# Block_Template.net
KiCad netlist of a schematic drawn in EAGLE
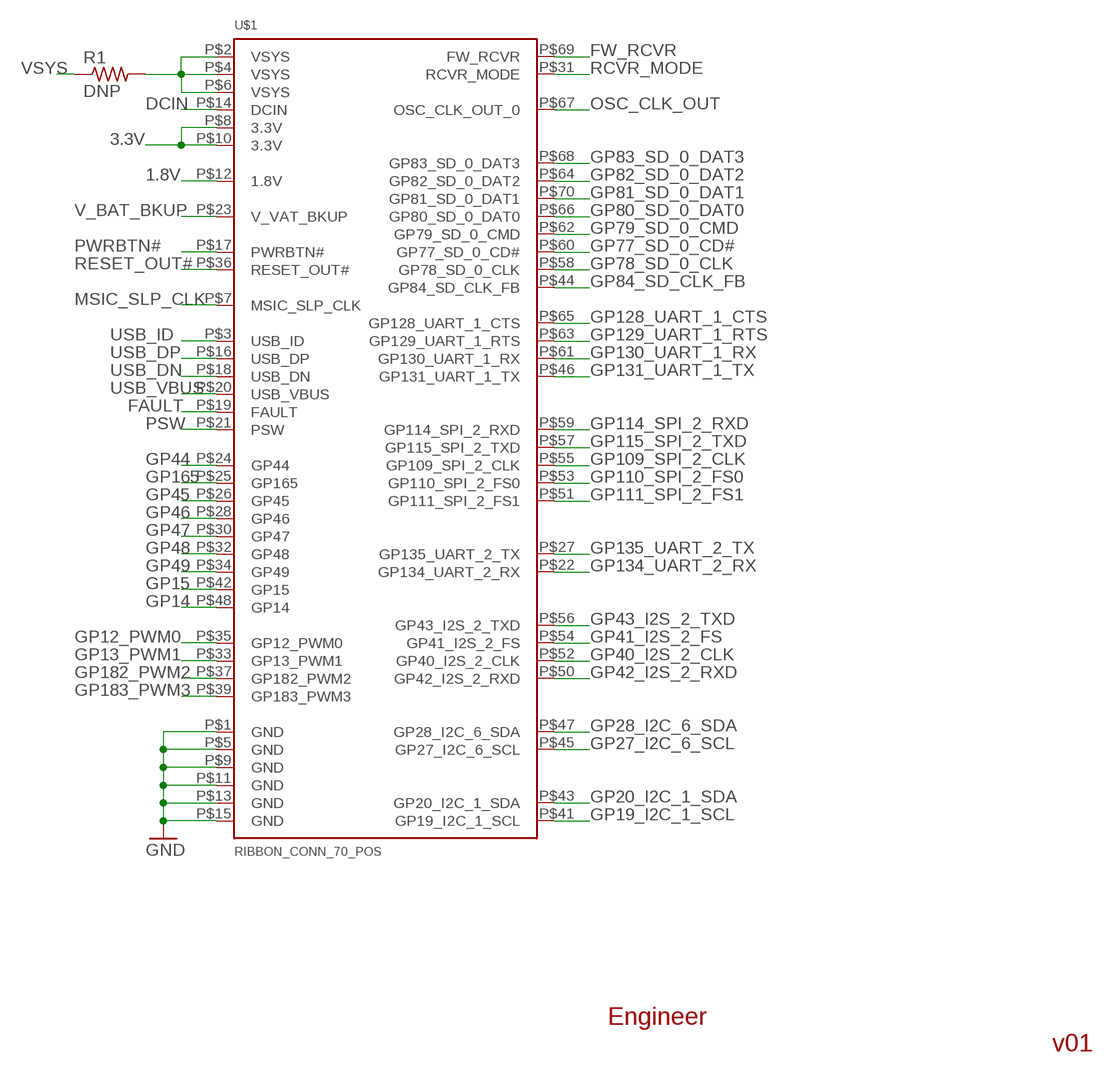
[diagram p0: schematic, sheet 1]
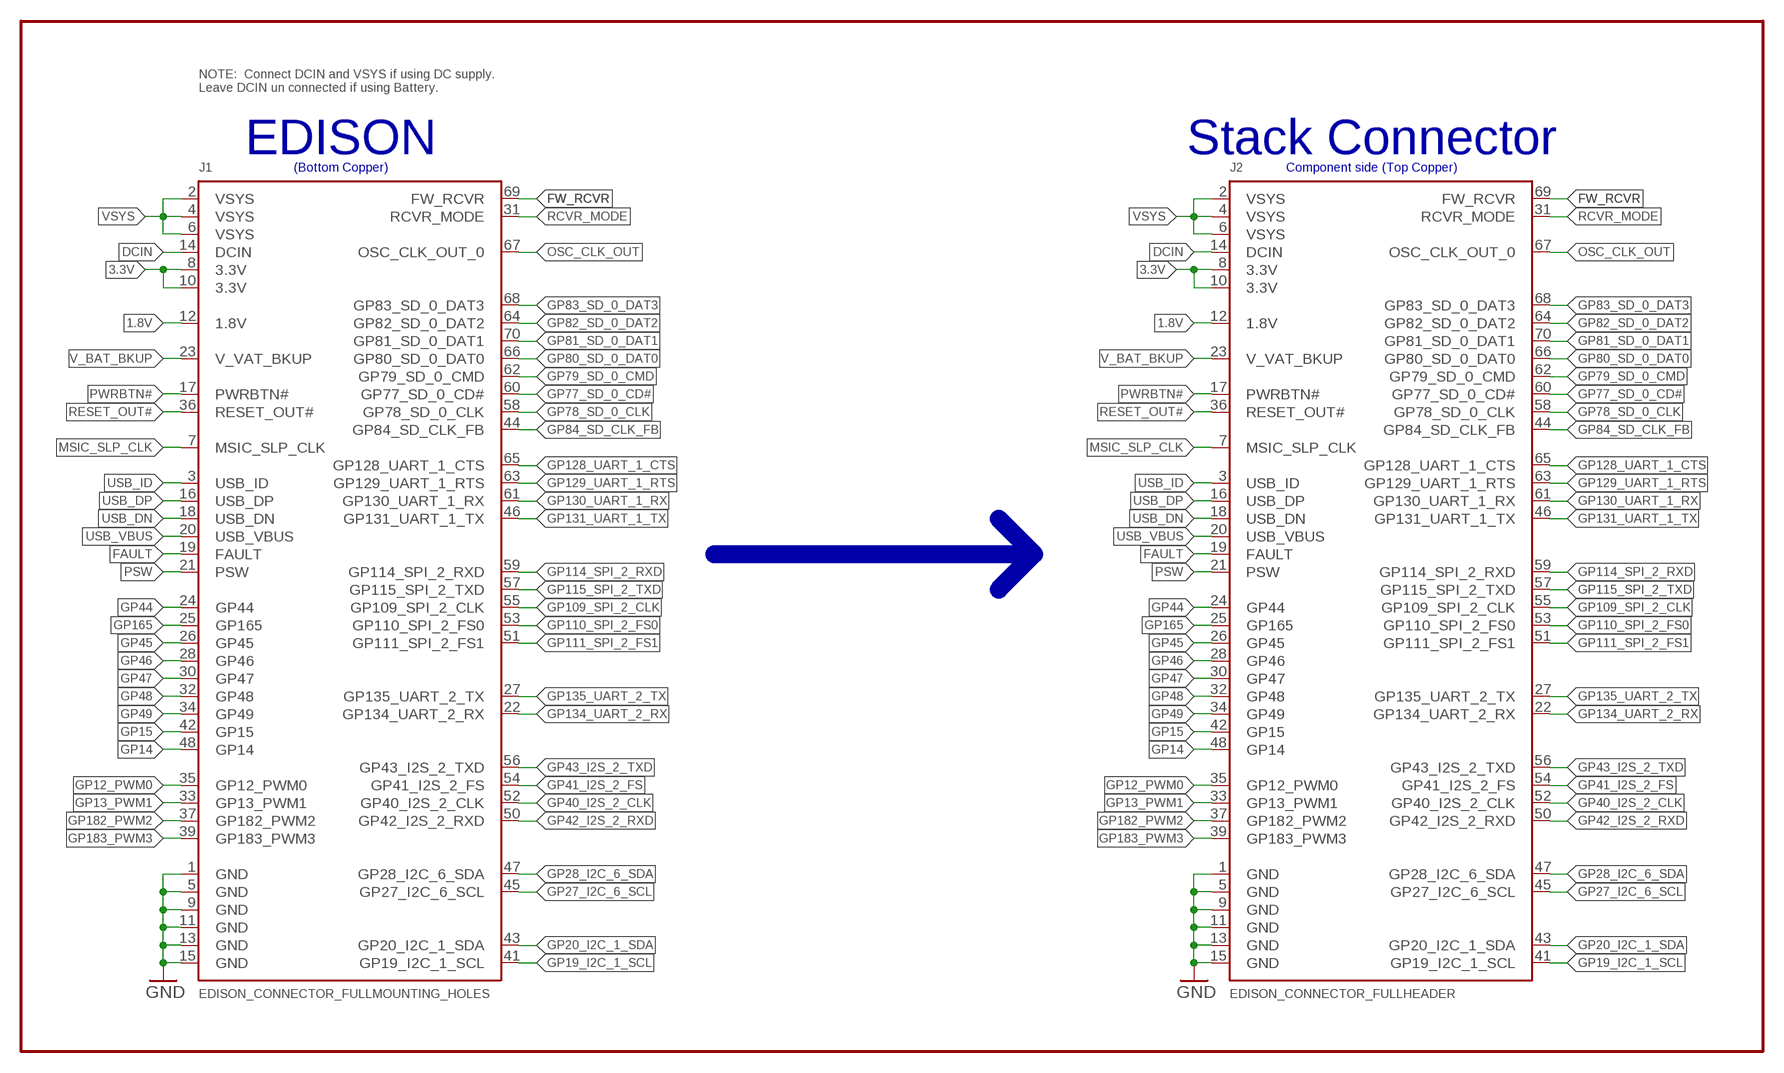
[diagram p1: schematic, sheet 2]

(export (version "E")
  (design (tool "Eeschema 10.0.6"))
  (components
    (comp (ref "J1")
      (value "EDISON_CONNECTOR_FULLMOUNTING_HOLES")
      (footprint "eagle-import:EDISON_DAUGHTER")
      (libsource (lib "eagle-import") (part "EDISON_CONNECTOR_FULLMOUNTING_HOLES"))
    )
    (comp (ref "J2")
      (value "EDISON_CONNECTOR_FULLHEADER")
      (footprint "eagle-import:DF40C-70DP-0.4(51)")
      (libsource (lib "eagle-import") (part "EDISON_CONNECTOR_FULLHEADER"))
    )
    (comp (ref "R1")
      (value "DNP")
      (footprint "eagle-import:R0402")
      (libsource (lib "eagle-import") (part "R-US_R0402"))
    )
    (comp (ref "U$1")
      (value "RIBBON_CONN_70_POS")
      (footprint "eagle-import:RIBBON_CONN_70_POS")
      (libsource (lib "eagle-import") (part "RIBBON_CONN_70_POS"))
    )
  )
  (nets
    (net (code "1") (name "1.8V") (class "Default")
      (node (ref "J1") (pin "12") (pinfunction "1.8V_12") (pintype "bidirectional"))
      (node (ref "J2") (pin "12") (pinfunction "1.8V_12") (pintype "bidirectional"))
      (node (ref "U$1") (pin "P$12") (pinfunction "1.8V_P$12") (pintype "bidirectional"))
    )
    (net (code "2") (name "3.3V") (class "Default")
      (node (ref "J1") (pin "10") (pinfunction "3.3V_10") (pintype "bidirectional"))
      (node (ref "J1") (pin "8") (pinfunction "3.3V_8") (pintype "bidirectional"))
      (node (ref "J2") (pin "10") (pinfunction "3.3V_10") (pintype "bidirectional"))
      (node (ref "J2") (pin "8") (pinfunction "3.3V_8") (pintype "bidirectional"))
      (node (ref "U$1") (pin "P$10") (pinfunction "3.3V_P$10") (pintype "bidirectional"))
      (node (ref "U$1") (pin "P$8") (pinfunction "3.3V_P$8") (pintype "bidirectional"))
    )
    (net (code "3") (name "DCIN") (class "Default")
      (node (ref "J1") (pin "14") (pinfunction "DCIN_14") (pintype "bidirectional"))
      (node (ref "J2") (pin "14") (pinfunction "DCIN_14") (pintype "bidirectional"))
      (node (ref "U$1") (pin "P$14") (pinfunction "DCIN_P$14") (pintype "bidirectional"))
    )
    (net (code "4") (name "FAULT") (class "Default")
      (node (ref "J1") (pin "19") (pinfunction "FAULT_19") (pintype "bidirectional"))
      (node (ref "J2") (pin "19") (pinfunction "FAULT_19") (pintype "bidirectional"))
      (node (ref "U$1") (pin "P$19") (pinfunction "FAULT_P$19") (pintype "bidirectional"))
    )
    (net (code "5") (name "FW_RCVR") (class "Default")
      (node (ref "J1") (pin "69") (pinfunction "FW_RCVR_69") (pintype "bidirectional"))
      (node (ref "J2") (pin "69") (pinfunction "FW_RCVR_69") (pintype "bidirectional"))
      (node (ref "U$1") (pin "P$69") (pinfunction "FW_RCVR_P$69") (pintype "bidirectional"))
    )
    (net (code "6") (name "GND") (class "Default")
      (node (ref "J1") (pin "1") (pinfunction "GND_1") (pintype "bidirectional"))
      (node (ref "J1") (pin "11") (pinfunction "GND_11") (pintype "bidirectional"))
      (node (ref "J1") (pin "13") (pinfunction "GND_13") (pintype "bidirectional"))
      (node (ref "J1") (pin "15") (pinfunction "GND_15") (pintype "bidirectional"))
      (node (ref "J1") (pin "5") (pinfunction "GND_5") (pintype "bidirectional"))
      (node (ref "J1") (pin "9") (pinfunction "GND_9") (pintype "bidirectional"))
      (node (ref "J2") (pin "1") (pinfunction "GND_1") (pintype "bidirectional"))
      (node (ref "J2") (pin "11") (pinfunction "GND_11") (pintype "bidirectional"))
      (node (ref "J2") (pin "13") (pinfunction "GND_13") (pintype "bidirectional"))
      (node (ref "J2") (pin "15") (pinfunction "GND_15") (pintype "bidirectional"))
      (node (ref "J2") (pin "5") (pinfunction "GND_5") (pintype "bidirectional"))
      (node (ref "J2") (pin "9") (pinfunction "GND_9") (pintype "bidirectional"))
      (node (ref "U$1") (pin "P$1") (pinfunction "GND_P$1") (pintype "bidirectional"))
      (node (ref "U$1") (pin "P$11") (pinfunction "GND_P$11") (pintype "bidirectional"))
      (node (ref "U$1") (pin "P$13") (pinfunction "GND_P$13") (pintype "bidirectional"))
      (node (ref "U$1") (pin "P$15") (pinfunction "GND_P$15") (pintype "bidirectional"))
      (node (ref "U$1") (pin "P$5") (pinfunction "GND_P$5") (pintype "bidirectional"))
      (node (ref "U$1") (pin "P$9") (pinfunction "GND_P$9") (pintype "bidirectional"))
    )
    (net (code "7") (name "GP12_PWM0") (class "Default")
      (node (ref "J1") (pin "35") (pinfunction "GP12_PWM0_35") (pintype "bidirectional"))
      (node (ref "J2") (pin "35") (pinfunction "GP12_PWM0_35") (pintype "bidirectional"))
      (node (ref "U$1") (pin "P$35") (pinfunction "GP12_PWM0_P$35") (pintype "bidirectional"))
    )
    (net (code "8") (name "GP13_PWM1") (class "Default")
      (node (ref "J1") (pin "33") (pinfunction "GP13_PWM1_33") (pintype "bidirectional"))
      (node (ref "J2") (pin "33") (pinfunction "GP13_PWM1_33") (pintype "bidirectional"))
      (node (ref "U$1") (pin "P$33") (pinfunction "GP13_PWM1_P$33") (pintype "bidirectional"))
    )
    (net (code "9") (name "GP14") (class "Default")
      (node (ref "J1") (pin "48") (pinfunction "GP14_48") (pintype "bidirectional"))
      (node (ref "J2") (pin "48") (pinfunction "GP14_48") (pintype "bidirectional"))
      (node (ref "U$1") (pin "P$48") (pinfunction "GP14_P$48") (pintype "bidirectional"))
    )
    (net (code "10") (name "GP15") (class "Default")
      (node (ref "J1") (pin "42") (pinfunction "GP15_42") (pintype "bidirectional"))
      (node (ref "J2") (pin "42") (pinfunction "GP15_42") (pintype "bidirectional"))
      (node (ref "U$1") (pin "P$42") (pinfunction "GP15_P$42") (pintype "bidirectional"))
    )
    (net (code "11") (name "GP19_I2C_1_SCL") (class "Default")
      (node (ref "J1") (pin "41") (pinfunction "GP19_I2C_1_SCL_41") (pintype "bidirectional"))
      (node (ref "J2") (pin "41") (pinfunction "GP19_I2C_1_SCL_41") (pintype "bidirectional"))
      (node (ref "U$1") (pin "P$41") (pinfunction "GP19_I2C_1_SCL_P$41") (pintype "bidirectional"))
    )
    (net (code "12") (name "GP20_I2C_1_SDA") (class "Default")
      (node (ref "J1") (pin "43") (pinfunction "GP20_I2C_1_SDA_43") (pintype "bidirectional"))
      (node (ref "J2") (pin "43") (pinfunction "GP20_I2C_1_SDA_43") (pintype "bidirectional"))
      (node (ref "U$1") (pin "P$43") (pinfunction "GP20_I2C_1_SDA_P$43") (pintype "bidirectional"))
    )
    (net (code "13") (name "GP27_I2C_6_SCL") (class "Default")
      (node (ref "J1") (pin "45") (pinfunction "GP27_I2C_6_SCL_45") (pintype "bidirectional"))
      (node (ref "J2") (pin "45") (pinfunction "GP27_I2C_6_SCL_45") (pintype "bidirectional"))
      (node (ref "U$1") (pin "P$45") (pinfunction "GP27_I2C_6_SCL_P$45") (pintype "bidirectional"))
    )
    (net (code "14") (name "GP28_I2C_6_SDA") (class "Default")
      (node (ref "J1") (pin "47") (pinfunction "GP28_I2C_6_SDA_47") (pintype "bidirectional"))
      (node (ref "J2") (pin "47") (pinfunction "GP28_I2C_6_SDA_47") (pintype "bidirectional"))
      (node (ref "U$1") (pin "P$47") (pinfunction "GP28_I2C_6_SDA_P$47") (pintype "bidirectional"))
    )
    (net (code "15") (name "GP40_I2S_2_CLK") (class "Default")
      (node (ref "J1") (pin "52") (pinfunction "GP40_I2S_2_CLK_52") (pintype "bidirectional"))
      (node (ref "J2") (pin "52") (pinfunction "GP40_I2S_2_CLK_52") (pintype "bidirectional"))
      (node (ref "U$1") (pin "P$52") (pinfunction "GP40_I2S_2_CLK_P$52") (pintype "bidirectional"))
    )
    (net (code "16") (name "GP41_I2S_2_FS") (class "Default")
      (node (ref "J1") (pin "54") (pinfunction "GP41_I2S_2_FS_54") (pintype "bidirectional"))
      (node (ref "J2") (pin "54") (pinfunction "GP41_I2S_2_FS_54") (pintype "bidirectional"))
      (node (ref "U$1") (pin "P$54") (pinfunction "GP41_I2S_2_FS_P$54") (pintype "bidirectional"))
    )
    (net (code "17") (name "GP42_I2S_2_RXD") (class "Default")
      (node (ref "J1") (pin "50") (pinfunction "GP42_I2S_2_RXD_50") (pintype "bidirectional"))
      (node (ref "J2") (pin "50") (pinfunction "GP42_I2S_2_RXD_50") (pintype "bidirectional"))
      (node (ref "U$1") (pin "P$50") (pinfunction "GP42_I2S_2_RXD_P$50") (pintype "bidirectional"))
    )
    (net (code "18") (name "GP43_I2S_2_TXD") (class "Default")
      (node (ref "J1") (pin "56") (pinfunction "GP43_I2S_2_TXD_56") (pintype "bidirectional"))
      (node (ref "J2") (pin "56") (pinfunction "GP43_I2S_2_TXD_56") (pintype "bidirectional"))
      (node (ref "U$1") (pin "P$56") (pinfunction "GP43_I2S_2_TXD_P$56") (pintype "bidirectional"))
    )
    (net (code "19") (name "GP44") (class "Default")
      (node (ref "J1") (pin "24") (pinfunction "GP44_24") (pintype "bidirectional"))
      (node (ref "J2") (pin "24") (pinfunction "GP44_24") (pintype "bidirectional"))
      (node (ref "U$1") (pin "P$24") (pinfunction "GP44_P$24") (pintype "bidirectional"))
    )
    (net (code "20") (name "GP45") (class "Default")
      (node (ref "J1") (pin "26") (pinfunction "GP45_26") (pintype "bidirectional"))
      (node (ref "J2") (pin "26") (pinfunction "GP45_26") (pintype "bidirectional"))
      (node (ref "U$1") (pin "P$26") (pinfunction "GP45_P$26") (pintype "bidirectional"))
    )
    (net (code "21") (name "GP46") (class "Default")
      (node (ref "J1") (pin "28") (pinfunction "GP46_28") (pintype "bidirectional"))
      (node (ref "J2") (pin "28") (pinfunction "GP46_28") (pintype "bidirectional"))
      (node (ref "U$1") (pin "P$28") (pinfunction "GP46_P$28") (pintype "bidirectional"))
    )
    (net (code "22") (name "GP47") (class "Default")
      (node (ref "J1") (pin "30") (pinfunction "GP47_30") (pintype "bidirectional"))
      (node (ref "J2") (pin "30") (pinfunction "GP47_30") (pintype "bidirectional"))
      (node (ref "U$1") (pin "P$30") (pinfunction "GP47_P$30") (pintype "bidirectional"))
    )
    (net (code "23") (name "GP48") (class "Default")
      (node (ref "J1") (pin "32") (pinfunction "GP48_32") (pintype "bidirectional"))
      (node (ref "J2") (pin "32") (pinfunction "GP48_32") (pintype "bidirectional"))
      (node (ref "U$1") (pin "P$32") (pinfunction "GP48_P$32") (pintype "bidirectional"))
    )
    (net (code "24") (name "GP49") (class "Default")
      (node (ref "J1") (pin "34") (pinfunction "GP49_34") (pintype "bidirectional"))
      (node (ref "J2") (pin "34") (pinfunction "GP49_34") (pintype "bidirectional"))
      (node (ref "U$1") (pin "P$34") (pinfunction "GP49_P$34") (pintype "bidirectional"))
    )
    (net (code "25") (name "GP77_SD_0_CD#") (class "Default")
      (node (ref "J1") (pin "60") (pinfunction "GP77_SD_0_CD#_60") (pintype "bidirectional"))
      (node (ref "J2") (pin "60") (pinfunction "GP77_SD_0_CD#_60") (pintype "bidirectional"))
      (node (ref "U$1") (pin "P$60") (pinfunction "GP77_SD_0_CD#_P$60") (pintype "bidirectional"))
    )
    (net (code "26") (name "GP78_SD_0_CLK") (class "Default")
      (node (ref "J1") (pin "58") (pinfunction "GP78_SD_0_CLK_58") (pintype "bidirectional"))
      (node (ref "J2") (pin "58") (pinfunction "GP78_SD_0_CLK_58") (pintype "bidirectional"))
      (node (ref "U$1") (pin "P$58") (pinfunction "GP78_SD_0_CLK_P$58") (pintype "bidirectional"))
    )
    (net (code "27") (name "GP79_SD_0_CMD") (class "Default")
      (node (ref "J1") (pin "62") (pinfunction "GP79_SD_0_CMD_62") (pintype "bidirectional"))
      (node (ref "J2") (pin "62") (pinfunction "GP79_SD_0_CMD_62") (pintype "bidirectional"))
      (node (ref "U$1") (pin "P$62") (pinfunction "GP79_SD_0_CMD_P$62") (pintype "bidirectional"))
    )
    (net (code "28") (name "GP80_SD_0_DAT0") (class "Default")
      (node (ref "J1") (pin "66") (pinfunction "GP80_SD_0_DAT0_66") (pintype "bidirectional"))
      (node (ref "J2") (pin "66") (pinfunction "GP80_SD_0_DAT0_66") (pintype "bidirectional"))
      (node (ref "U$1") (pin "P$66") (pinfunction "GP80_SD_0_DAT0_P$66") (pintype "bidirectional"))
    )
    (net (code "29") (name "GP81_SD_0_DAT1") (class "Default")
      (node (ref "J1") (pin "70") (pinfunction "GP81_SD_0_DAT1_70") (pintype "bidirectional"))
      (node (ref "J2") (pin "70") (pinfunction "GP81_SD_0_DAT1_70") (pintype "bidirectional"))
      (node (ref "U$1") (pin "P$70") (pinfunction "GP81_SD_0_DAT1_P$70") (pintype "bidirectional"))
    )
    (net (code "30") (name "GP82_SD_0_DAT2") (class "Default")
      (node (ref "J1") (pin "64") (pinfunction "GP82_SD_0_DAT2_64") (pintype "bidirectional"))
      (node (ref "J2") (pin "64") (pinfunction "GP82_SD_0_DAT2_64") (pintype "bidirectional"))
      (node (ref "U$1") (pin "P$64") (pinfunction "GP82_SD_0_DAT2_P$64") (pintype "bidirectional"))
    )
    (net (code "31") (name "GP83_SD_0_DAT3") (class "Default")
      (node (ref "J1") (pin "68") (pinfunction "GP83_SD_0_DAT3_68") (pintype "bidirectional"))
      (node (ref "J2") (pin "68") (pinfunction "GP83_SD_0_DAT3_68") (pintype "bidirectional"))
      (node (ref "U$1") (pin "P$68") (pinfunction "GP83_SD_0_DAT3_P$68") (pintype "bidirectional"))
    )
    (net (code "32") (name "GP84_SD_CLK_FB") (class "Default")
      (node (ref "J1") (pin "44") (pinfunction "GP84_SD_CLK_FB_44") (pintype "bidirectional"))
      (node (ref "J2") (pin "44") (pinfunction "GP84_SD_CLK_FB_44") (pintype "bidirectional"))
      (node (ref "U$1") (pin "P$44") (pinfunction "GP84_SD_CLK_FB_P$44") (pintype "bidirectional"))
    )
    (net (code "33") (name "GP109_SPI_2_CLK") (class "Default")
      (node (ref "J1") (pin "55") (pinfunction "GP109_SPI_2_CLK_55") (pintype "bidirectional"))
      (node (ref "J2") (pin "55") (pinfunction "GP109_SPI_2_CLK_55") (pintype "bidirectional"))
      (node (ref "U$1") (pin "P$55") (pinfunction "GP109_SPI_2_CLK_P$55") (pintype "bidirectional"))
    )
    (net (code "34") (name "GP110_SPI_2_FS0") (class "Default")
      (node (ref "J1") (pin "53") (pinfunction "GP110_SPI_2_FS0_53") (pintype "bidirectional"))
      (node (ref "J2") (pin "53") (pinfunction "GP110_SPI_2_FS0_53") (pintype "bidirectional"))
      (node (ref "U$1") (pin "P$53") (pinfunction "GP110_SPI_2_FS0_P$53") (pintype "bidirectional"))
    )
    (net (code "35") (name "GP111_SPI_2_FS1") (class "Default")
      (node (ref "J1") (pin "51") (pinfunction "GP111_SPI_2_FS1_51") (pintype "bidirectional"))
      (node (ref "J2") (pin "51") (pinfunction "GP111_SPI_2_FS1_51") (pintype "bidirectional"))
      (node (ref "U$1") (pin "P$51") (pinfunction "GP111_SPI_2_FS1_P$51") (pintype "bidirectional"))
    )
    (net (code "36") (name "GP114_SPI_2_RXD") (class "Default")
      (node (ref "J1") (pin "59") (pinfunction "GP114_SPI_2_RXD_59") (pintype "bidirectional"))
      (node (ref "J2") (pin "59") (pinfunction "GP114_SPI_2_RXD_59") (pintype "bidirectional"))
      (node (ref "U$1") (pin "P$59") (pinfunction "GP114_SPI_2_RXD_P$59") (pintype "bidirectional"))
    )
    (net (code "37") (name "GP115_SPI_2_TXD") (class "Default")
      (node (ref "J1") (pin "57") (pinfunction "GP115_SPI_2_TXD_57") (pintype "bidirectional"))
      (node (ref "J2") (pin "57") (pinfunction "GP115_SPI_2_TXD_57") (pintype "bidirectional"))
      (node (ref "U$1") (pin "P$57") (pinfunction "GP115_SPI_2_TXD_P$57") (pintype "bidirectional"))
    )
    (net (code "38") (name "GP128_UART_1_CTS") (class "Default")
      (node (ref "J1") (pin "65") (pinfunction "GP128_UART_1_CTS_65") (pintype "bidirectional"))
      (node (ref "J2") (pin "65") (pinfunction "GP128_UART_1_CTS_65") (pintype "bidirectional"))
      (node (ref "U$1") (pin "P$65") (pinfunction "GP128_UART_1_CTS_P$65") (pintype "bidirectional"))
    )
    (net (code "39") (name "GP129_UART_1_RTS") (class "Default")
      (node (ref "J1") (pin "63") (pinfunction "GP129_UART_1_RTS_63") (pintype "bidirectional"))
      (node (ref "J2") (pin "63") (pinfunction "GP129_UART_1_RTS_63") (pintype "bidirectional"))
      (node (ref "U$1") (pin "P$63") (pinfunction "GP129_UART_1_RTS_P$63") (pintype "bidirectional"))
    )
    (net (code "40") (name "GP130_UART_1_RX") (class "Default")
      (node (ref "J1") (pin "61") (pinfunction "GP130_UART_1_RX_61") (pintype "bidirectional"))
      (node (ref "J2") (pin "61") (pinfunction "GP130_UART_1_RX_61") (pintype "bidirectional"))
      (node (ref "U$1") (pin "P$61") (pinfunction "GP130_UART_1_RX_P$61") (pintype "bidirectional"))
    )
    (net (code "41") (name "GP131_UART_1_TX") (class "Default")
      (node (ref "J1") (pin "46") (pinfunction "GP131_UART_1_TX_46") (pintype "bidirectional"))
      (node (ref "J2") (pin "46") (pinfunction "GP131_UART_1_TX_46") (pintype "bidirectional"))
      (node (ref "U$1") (pin "P$46") (pinfunction "GP131_UART_1_TX_P$46") (pintype "bidirectional"))
    )
    (net (code "42") (name "GP134_UART_2_RX") (class "Default")
      (node (ref "J1") (pin "22") (pinfunction "GP134_UART_2_RX_22") (pintype "bidirectional"))
      (node (ref "J2") (pin "22") (pinfunction "GP134_UART_2_RX_22") (pintype "bidirectional"))
      (node (ref "U$1") (pin "P$22") (pinfunction "GP134_UART_2_RX_P$22") (pintype "bidirectional"))
    )
    (net (code "43") (name "GP135_UART_2_TX") (class "Default")
      (node (ref "J1") (pin "27") (pinfunction "GP135_UART_2_TX_27") (pintype "bidirectional"))
      (node (ref "J2") (pin "27") (pinfunction "GP135_UART_2_TX_27") (pintype "bidirectional"))
      (node (ref "U$1") (pin "P$27") (pinfunction "GP135_UART_2_TX_P$27") (pintype "bidirectional"))
    )
    (net (code "44") (name "GP165") (class "Default")
      (node (ref "J1") (pin "25") (pinfunction "GP165_25") (pintype "bidirectional"))
      (node (ref "J2") (pin "25") (pinfunction "GP165_25") (pintype "bidirectional"))
      (node (ref "U$1") (pin "P$25") (pinfunction "GP165_P$25") (pintype "bidirectional"))
    )
    (net (code "45") (name "GP182_PWM2") (class "Default")
      (node (ref "J1") (pin "37") (pinfunction "GP182_PWM2_37") (pintype "bidirectional"))
      (node (ref "J2") (pin "37") (pinfunction "GP182_PWM2_37") (pintype "bidirectional"))
      (node (ref "U$1") (pin "P$37") (pinfunction "GP182_PWM2_P$37") (pintype "bidirectional"))
    )
    (net (code "46") (name "GP183_PWM3") (class "Default")
      (node (ref "J1") (pin "39") (pinfunction "GP183_PWM3_39") (pintype "bidirectional"))
      (node (ref "J2") (pin "39") (pinfunction "GP183_PWM3_39") (pintype "bidirectional"))
      (node (ref "U$1") (pin "P$39") (pinfunction "GP183_PWM3_P$39") (pintype "bidirectional"))
    )
    (net (code "47") (name "MSIC_SLP_CLK") (class "Default")
      (node (ref "J1") (pin "7") (pinfunction "MSIC_SLP_CLK_7") (pintype "bidirectional"))
      (node (ref "J2") (pin "7") (pinfunction "MSIC_SLP_CLK_7") (pintype "bidirectional"))
      (node (ref "U$1") (pin "P$7") (pinfunction "MSIC_SLP_CLK_P$7") (pintype "bidirectional"))
    )
    (net (code "48") (name "Net-(R1-Pad2)") (class "Default")
      (node (ref "R1") (pin "2") (pinfunction "2_2") (pintype "passive"))
      (node (ref "U$1") (pin "P$2") (pinfunction "VSYS_P$2") (pintype "bidirectional"))
      (node (ref "U$1") (pin "P$4") (pinfunction "VSYS_P$4") (pintype "bidirectional"))
      (node (ref "U$1") (pin "P$6") (pinfunction "VSYS_P$6") (pintype "bidirectional"))
    )
    (net (code "49") (name "OSC_CLK_OUT") (class "Default")
      (node (ref "J1") (pin "67") (pinfunction "OSC_CLK_OUT_0_67") (pintype "bidirectional"))
      (node (ref "J2") (pin "67") (pinfunction "OSC_CLK_OUT_0_67") (pintype "bidirectional"))
      (node (ref "U$1") (pin "P$67") (pinfunction "OSC_CLK_OUT_0_P$67") (pintype "bidirectional"))
    )
    (net (code "50") (name "PSW") (class "Default")
      (node (ref "J1") (pin "21") (pinfunction "PSW_21") (pintype "bidirectional"))
      (node (ref "J2") (pin "21") (pinfunction "PSW_21") (pintype "bidirectional"))
      (node (ref "U$1") (pin "P$21") (pinfunction "PSW_P$21") (pintype "bidirectional"))
    )
    (net (code "51") (name "PWRBTN#") (class "Default")
      (node (ref "J1") (pin "17") (pinfunction "PWRBTN#_17") (pintype "bidirectional"))
      (node (ref "J2") (pin "17") (pinfunction "PWRBTN#_17") (pintype "bidirectional"))
      (node (ref "U$1") (pin "P$17") (pinfunction "PWRBTN#_P$17") (pintype "bidirectional"))
    )
    (net (code "52") (name "RCVR_MODE") (class "Default")
      (node (ref "J1") (pin "31") (pinfunction "RCVR_MODE_31") (pintype "bidirectional"))
      (node (ref "J2") (pin "31") (pinfunction "RCVR_MODE_31") (pintype "bidirectional"))
      (node (ref "U$1") (pin "P$31") (pinfunction "RCVR_MODE_P$31") (pintype "bidirectional"))
    )
    (net (code "53") (name "RESET_OUT#") (class "Default")
      (node (ref "J1") (pin "36") (pinfunction "RESET_OUT#_36") (pintype "bidirectional"))
      (node (ref "J2") (pin "36") (pinfunction "RESET_OUT#_36") (pintype "bidirectional"))
      (node (ref "U$1") (pin "P$36") (pinfunction "RESET_OUT#_P$36") (pintype "bidirectional"))
    )
    (net (code "54") (name "USB_DN") (class "Default")
      (node (ref "J1") (pin "18") (pinfunction "USB_DN_18") (pintype "bidirectional"))
      (node (ref "J2") (pin "18") (pinfunction "USB_DN_18") (pintype "bidirectional"))
      (node (ref "U$1") (pin "P$18") (pinfunction "USB_DN_P$18") (pintype "bidirectional"))
    )
    (net (code "55") (name "USB_DP") (class "Default")
      (node (ref "J1") (pin "16") (pinfunction "USB_DP_16") (pintype "bidirectional"))
      (node (ref "J2") (pin "16") (pinfunction "USB_DP_16") (pintype "bidirectional"))
      (node (ref "U$1") (pin "P$16") (pinfunction "USB_DP_P$16") (pintype "bidirectional"))
    )
    (net (code "56") (name "USB_ID") (class "Default")
      (node (ref "J1") (pin "3") (pinfunction "USB_ID_3") (pintype "bidirectional"))
      (node (ref "J2") (pin "3") (pinfunction "USB_ID_3") (pintype "bidirectional"))
      (node (ref "U$1") (pin "P$3") (pinfunction "USB_ID_P$3") (pintype "bidirectional"))
    )
    (net (code "57") (name "USB_VBUS") (class "Default")
      (node (ref "J1") (pin "20") (pinfunction "USB_VBUS_20") (pintype "bidirectional"))
      (node (ref "J2") (pin "20") (pinfunction "USB_VBUS_20") (pintype "bidirectional"))
      (node (ref "U$1") (pin "P$20") (pinfunction "USB_VBUS_P$20") (pintype "bidirectional"))
    )
    (net (code "58") (name "VSYS") (class "Default")
      (node (ref "J1") (pin "2") (pinfunction "VSYS_2") (pintype "bidirectional"))
      (node (ref "J1") (pin "4") (pinfunction "VSYS_4") (pintype "bidirectional"))
      (node (ref "J1") (pin "6") (pinfunction "VSYS_6") (pintype "bidirectional"))
      (node (ref "J2") (pin "2") (pinfunction "VSYS_2") (pintype "bidirectional"))
      (node (ref "J2") (pin "4") (pinfunction "VSYS_4") (pintype "bidirectional"))
      (node (ref "J2") (pin "6") (pinfunction "VSYS_6") (pintype "bidirectional"))
      (node (ref "R1") (pin "1") (pinfunction "1_1") (pintype "passive"))
    )
    (net (code "59") (name "V_BAT_BKUP") (class "Default")
      (node (ref "J1") (pin "23") (pinfunction "V_VAT_BKUP_23") (pintype "bidirectional"))
      (node (ref "J2") (pin "23") (pinfunction "V_VAT_BKUP_23") (pintype "bidirectional"))
      (node (ref "U$1") (pin "P$23") (pinfunction "V_VAT_BKUP_P$23") (pintype "bidirectional"))
    )
  )
)
